# Sheet1_Overview.net
KiCad netlist of a schematic drawn in Altium Designer
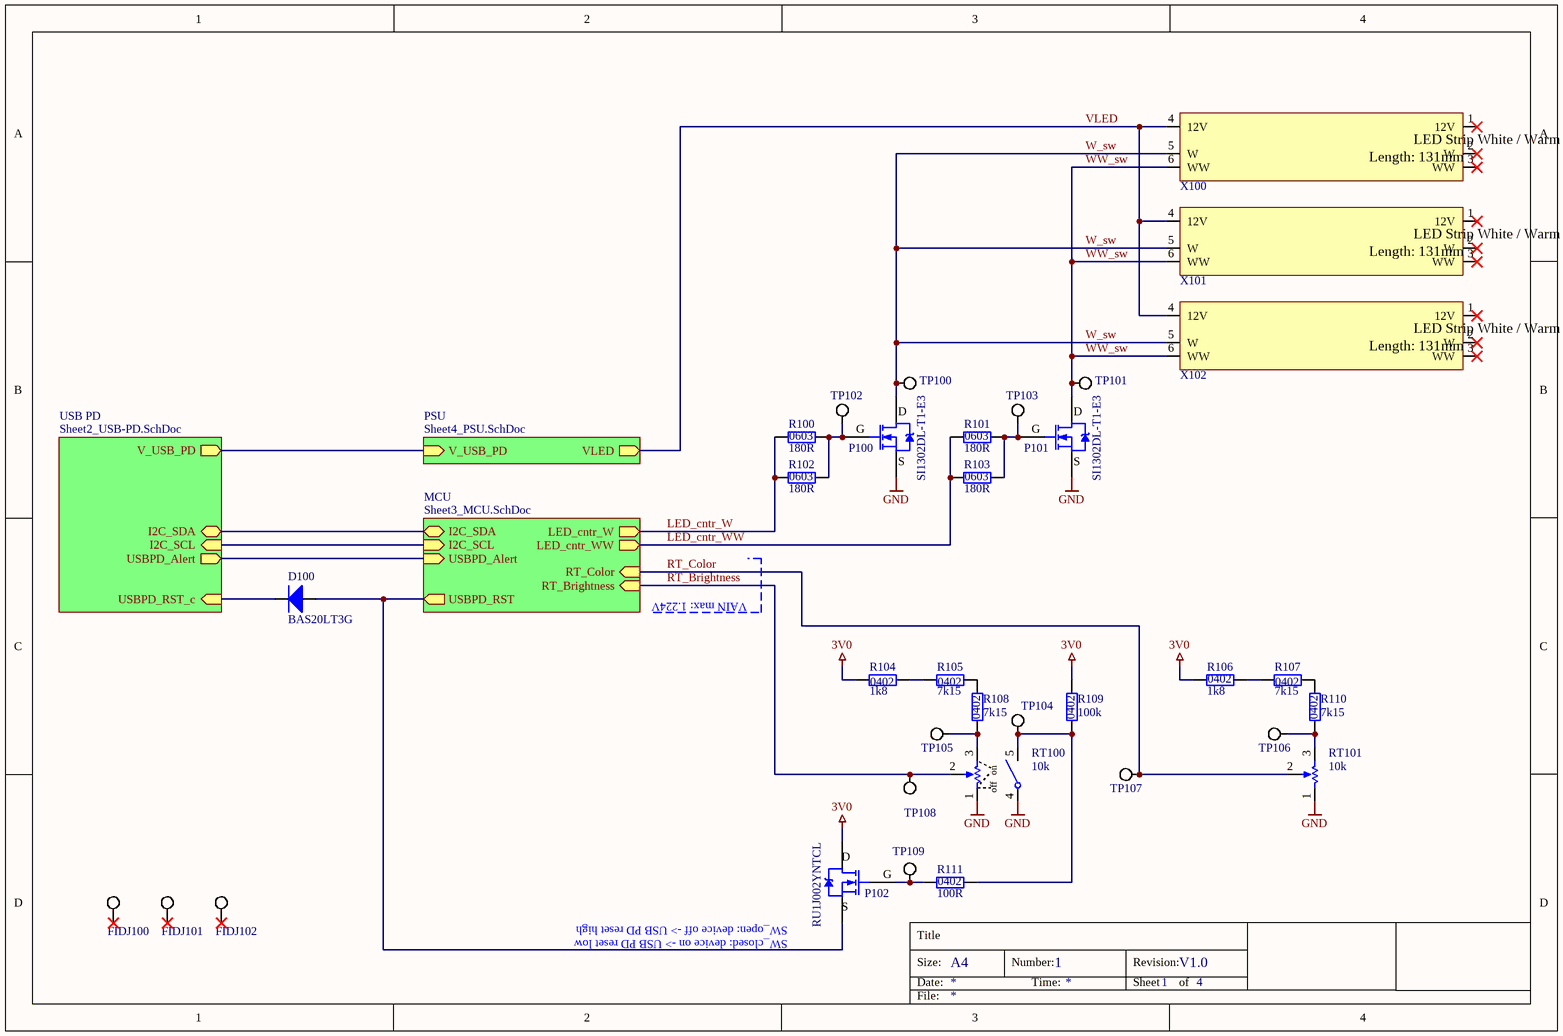
[diagram p0: Sheet1_Overview.SchDoc]

(export (version "E")
  (design (tool "Eeschema 10.0.6"))
  (components
    (comp (ref "D100")
      (value "BAS20LT3G")
      (footprint "SOT-23-3")
      (description "DIODE GP 200V 200MA SOT23-3")
      (fields (field (name "MANUFACTURER") "onsemi") (field (name "MANUFACTURER PART NUMBER") "BAS20LT3G"))
      (libsource (lib "CS_Part_Library") (part "D_LL_200V_200mA"))
    )
    (comp (ref "FIDJ100")
      (value "Fiducial")
      (footprint "FIDJ_1mm")
      (description "Fiducal 1mm")
      (libsource (lib "CS_Part_Library") (part "FIDJ_1mm"))
    )
    (comp (ref "FIDJ101")
      (value "Fiducial")
      (footprint "FIDJ_1mm")
      (description "Fiducal 1mm")
      (libsource (lib "CS_Part_Library") (part "FIDJ_1mm"))
    )
    (comp (ref "FIDJ102")
      (value "Fiducial")
      (footprint "FIDJ_1mm")
      (description "Fiducal 1mm")
      (libsource (lib "CS_Part_Library") (part "FIDJ_1mm"))
    )
    (comp (ref "P100")
      (value "P NMOS 30V 600mA")
      (footprint "SOT-323")
      (description "MOSFET N-CH 30V 600MA SC70-3")
      (fields
        (field (name "MANUFACTURER") "Vishay Siliconix")
        (field (name "MANUFACTURER PART NUMBER") "SI1302DL-T1-E3")
      )
      (libsource (lib "CS_Part_Library") (part "P_NCH_30V_280mW"))
    )
    (comp (ref "P101")
      (value "P NMOS 30V 600mA")
      (footprint "SOT-323")
      (description "MOSFET N-CH 30V 600MA SC70-3")
      (fields
        (field (name "MANUFACTURER") "Vishay Siliconix")
        (field (name "MANUFACTURER PART NUMBER") "SI1302DL-T1-E3")
      )
      (libsource (lib "CS_Part_Library") (part "P_NCH_30V_280mW"))
    )
    (comp (ref "P102")
      (value "P_NCH_50V_150mW")
      (footprint "UMT3F")
      (description "MOSFET N-CH 50V 200MA UMT3F")
      (fields
        (field (name "MANUFACTURER") "Rohm Semiconductor")
        (field (name "MANUFACTURER PART NUMBER") "RU1J002YNTCL")
      )
      (libsource (lib "CS_Part_Library") (part "P_NCH_50V_150mW"))
    )
    (comp (ref "R100")
      (value "R 180R 0603")
      (footprint "0603")
      (description "RES 180 OHM 1% 1/10W 0603")
      (fields
        (field (name "MANUFACTURER") "Stackpole Electronics Inc")
        (field (name "MANUFACTURER PART NUMBER") "RMCF0603FT180R")
        (field (name "RESISTANCE") "180R")
      )
      (libsource (lib "CS_Part_Library") (part "R_180R_0603"))
    )
    (comp (ref "R101")
      (value "R 180R 0603")
      (footprint "0603")
      (description "RES 180 OHM 1% 1/10W 0603")
      (fields
        (field (name "MANUFACTURER") "Stackpole Electronics Inc")
        (field (name "MANUFACTURER PART NUMBER") "RMCF0603FT180R")
        (field (name "RESISTANCE") "180R")
      )
      (libsource (lib "CS_Part_Library") (part "R_180R_0603"))
    )
    (comp (ref "R102")
      (value "R 180R 0603")
      (footprint "0603")
      (description "RES 180 OHM 1% 1/10W 0603")
      (fields
        (field (name "MANUFACTURER") "Stackpole Electronics Inc")
        (field (name "MANUFACTURER PART NUMBER") "RMCF0603FT180R")
        (field (name "RESISTANCE") "180R")
      )
      (libsource (lib "CS_Part_Library") (part "R_180R_0603"))
    )
    (comp (ref "R103")
      (value "R 180R 0603")
      (footprint "0603")
      (description "RES 180 OHM 1% 1/10W 0603")
      (fields
        (field (name "MANUFACTURER") "Stackpole Electronics Inc")
        (field (name "MANUFACTURER PART NUMBER") "RMCF0603FT180R")
        (field (name "RESISTANCE") "180R")
      )
      (libsource (lib "CS_Part_Library") (part "R_180R_0603"))
    )
    (comp (ref "R104")
      (value "R 1k8 0402")
      (footprint "0402")
      (description "RES 1.8K OHM 1% 1/16W 0402")
      (fields
        (field (name "MANUFACTURER") "Stackpole Electronics Inc")
        (field (name "MANUFACTURER PART NUMBER") "RMCF0402FT1K80")
        (field (name "RESISTANCE") "1k8")
      )
      (libsource (lib "") (part "R_1k8_0402_1"))
    )
    (comp (ref "R105")
      (value "R 7k15 0402")
      (footprint "0402")
      (description "RES 7.15K OHM 1% 1/16W 0402")
      (fields
        (field (name "MANUFACTURER") "Stackpole Electronics Inc")
        (field (name "MANUFACTURER PART NUMBER") "RMCF0402FT7K15")
        (field (name "RESISTANCE") "7k15")
      )
      (libsource (lib "") (part "R_7k15_0402_1"))
    )
    (comp (ref "R106")
      (value "R 1k8 0402")
      (footprint "0402")
      (description "RES 1.8K OHM 1% 1/16W 0402")
      (fields
        (field (name "MANUFACTURER") "Stackpole Electronics Inc")
        (field (name "MANUFACTURER PART NUMBER") "RMCF0402FT1K80")
        (field (name "RESISTANCE") "1k8")
      )
      (libsource (lib "CS_Part_Library") (part "R_1k8_0402"))
    )
    (comp (ref "R107")
      (value "R 7k15 0402")
      (footprint "0402")
      (description "RES 7.15K OHM 1% 1/16W 0402")
      (fields
        (field (name "MANUFACTURER") "Stackpole Electronics Inc")
        (field (name "MANUFACTURER PART NUMBER") "RMCF0402FT7K15")
        (field (name "RESISTANCE") "7k15")
      )
      (libsource (lib "") (part "R_7k15_0402_1"))
    )
    (comp (ref "R108")
      (value "R 7k15 0402")
      (footprint "0402")
      (description "RES 7.15K OHM 1% 1/16W 0402")
      (fields
        (field (name "MANUFACTURER") "Stackpole Electronics Inc")
        (field (name "MANUFACTURER PART NUMBER") "RMCF0402FT7K15")
        (field (name "RESISTANCE") "7k15")
      )
      (libsource (lib "CS_Part_Library") (part "R_7k15_0402"))
    )
    (comp (ref "R109")
      (value "R 100k 0402")
      (footprint "0402")
      (description "RES 100K OHM 5% 1/16W 0402")
      (fields
        (field (name "MANUFACTURER") "YAGEO")
        (field (name "MANUFACTURER PART NUMBER") "RC0402JR-07100KL")
        (field (name "RESISTANCE") "100k")
      )
      (libsource (lib "CS_Part_Library") (part "R_100k_0402"))
    )
    (comp (ref "R110")
      (value "R 7k15 0402")
      (footprint "0402")
      (description "RES 7.15K OHM 1% 1/16W 0402")
      (fields
        (field (name "MANUFACTURER") "Stackpole Electronics Inc")
        (field (name "MANUFACTURER PART NUMBER") "RMCF0402FT7K15")
        (field (name "RESISTANCE") "7k15")
      )
      (libsource (lib "CS_Part_Library") (part "R_7k15_0402"))
    )
    (comp (ref "R111")
      (value "R 100R 0402")
      (footprint "0402")
      (description "RES 100 OHM 1% 1/16W 0402")
      (fields
        (field (name "MANUFACTURER") "Stackpole Electronics Inc")
        (field (name "MANUFACTURER PART NUMBER") "RMCF0402FT100R")
        (field (name "RESISTANCE") "100R")
      )
      (libsource (lib "CS_Part_Library") (part "R_100R_0402"))
    )
    (comp (ref "RT100")
      (value "10k")
      (footprint "RT_P091S-F*20")
      (description "POT 10K OHM 1/20W PLASTIC LINEAR")
      (fields
        (field (name "MANUFACTURER") "TT Electronics/BI")
        (field (name "MANUFACTURER PART NUMBER") "P091S-FC20BR10K")
      )
      (libsource (lib "CS_Part_Library") (part "RT_10k_SW_V"))
    )
    (comp (ref "RT101")
      (value "10k")
      (footprint "RT_P091N-F*25")
      (description "POT 10K OHM 1/20W PLASTIC LINEAR")
      (fields
        (field (name "MANUFACTURER") "TT Electronics/BI")
        (field (name "MANUFACTURER PART NUMBER") "P091N-FC25BR10K")
      )
      (libsource (lib "CS_Part_Library") (part "RT_10k_V"))
    )
    (comp (ref "TP100")
      (value "TP")
      (footprint "TP_1mm")
      (description "Test Point 1mm")
      (libsource (lib "CS_Part_Library") (part "TP_1mm"))
    )
    (comp (ref "TP101")
      (value "TP")
      (footprint "TP_1mm")
      (description "Test Point 1mm")
      (libsource (lib "CS_Part_Library") (part "TP_1mm"))
    )
    (comp (ref "TP102")
      (value "TP")
      (footprint "TP_1mm")
      (description "Test Point 1mm")
      (libsource (lib "CS_Part_Library") (part "TP_1mm"))
    )
    (comp (ref "TP103")
      (value "TP")
      (footprint "TP_1mm")
      (description "Test Point 1mm")
      (libsource (lib "CS_Part_Library") (part "TP_1mm"))
    )
    (comp (ref "TP104")
      (value "TP")
      (footprint "TP_1mm")
      (description "Test Point 1mm")
      (libsource (lib "CS_Part_Library") (part "TP_1mm"))
    )
    (comp (ref "TP105")
      (value "TP")
      (footprint "TP_1mm")
      (description "Test Point 1mm")
      (libsource (lib "CS_Part_Library") (part "TP_1mm"))
    )
    (comp (ref "TP106")
      (value "TP")
      (footprint "TP_1mm")
      (description "Test Point 1mm")
      (libsource (lib "CS_Part_Library") (part "TP_1mm"))
    )
    (comp (ref "TP107")
      (value "TP")
      (footprint "TP_1mm")
      (description "Test Point 1mm")
      (libsource (lib "CS_Part_Library") (part "TP_1mm"))
    )
    (comp (ref "TP108")
      (value "TP")
      (footprint "TP_1mm")
      (description "Test Point 1mm")
      (libsource (lib "CS_Part_Library") (part "TP_1mm"))
    )
    (comp (ref "TP109")
      (value "TP")
      (footprint "TP_1mm")
      (description "Test Point 1mm")
      (libsource (lib "CS_Part_Library") (part "TP_1mm"))
    )
    (comp (ref "X100")
      (value "LED Strip")
      (footprint "LED_Strip_COB44-076")
      (description "revoART, 12V COB LED Streifen - einstellbare Farbtemperatur - alle 1,3cm teilbar - 10mm breit")
      (fields (field (name "MANUFACTURER") "revoART") (field (name "MANUFACTURER PART NUMBER") "COB44-076"))
      (libsource (lib "CS_Part_Library") (part "LED_Strip_2WH_131mm"))
    )
    (comp (ref "X101")
      (value "LED Strip")
      (footprint "LED_Strip_COB44-076")
      (description "revoART, 12V COB LED Streifen - einstellbare Farbtemperatur - alle 1,3cm teilbar - 10mm breit")
      (fields (field (name "MANUFACTURER") "revoART") (field (name "MANUFACTURER PART NUMBER") "COB44-076"))
      (libsource (lib "CS_Part_Library") (part "LED_Strip_2WH_131mm"))
    )
    (comp (ref "X102")
      (value "LED Strip")
      (footprint "LED_Strip_COB44-076")
      (description "revoART, 12V COB LED Streifen - einstellbare Farbtemperatur - alle 1,3cm teilbar - 10mm breit")
      (fields (field (name "MANUFACTURER") "revoART") (field (name "MANUFACTURER PART NUMBER") "COB44-076"))
      (libsource (lib "CS_Part_Library") (part "LED_Strip_2WH_131mm"))
    )
  )
  (nets
    (net (code "3") (name "/LED_cntr_W") (class "Default")
      (node (ref "R100") (pin "1") (pinfunction "1_1") (pintype "passive"))
      (node (ref "R102") (pin "1") (pinfunction "1_1") (pintype "passive"))
    )
    (net (code "4") (name "/LED_cntr_WW") (class "Default")
      (node (ref "R101") (pin "1") (pinfunction "1_1") (pintype "passive"))
      (node (ref "R103") (pin "1") (pinfunction "1_1") (pintype "passive"))
    )
    (net (code "5") (name "/RT_Brightness") (class "Default")
      (node (ref "RT100") (pin "2") (pinfunction "2_2") (pintype "passive"))
      (node (ref "TP108") (pin "1") (pinfunction "TP_1") (pintype "passive"))
    )
    (net (code "6") (name "/RT_Color") (class "Default")
      (node (ref "RT101") (pin "2") (pinfunction "2_2") (pintype "passive"))
      (node (ref "TP107") (pin "1") (pinfunction "TP_1") (pintype "passive"))
    )
    (net (code "8") (name "/USBPD_RST") (class "Default")
      (node (ref "D100") (pin "1") (pinfunction "A_1") (pintype "passive"))
      (node (ref "P102") (pin "2") (pinfunction "S_2") (pintype "passive"))
    )
    (net (code "9") (name "/USBPD_RST_c") (class "Default")
      (node (ref "D100") (pin "3") (pinfunction "K_3") (pintype "passive"))
    )
    (net (code "10") (name "/VLED") (class "Default")
      (node (ref "X100") (pin "4") (pinfunction "12V_4") (pintype "passive"))
      (node (ref "X101") (pin "4") (pinfunction "12V_4") (pintype "passive"))
      (node (ref "X102") (pin "4") (pinfunction "12V_4") (pintype "passive"))
    )
    (net (code "12") (name "/WW_sw") (class "Default")
      (node (ref "P101") (pin "3") (pinfunction "D_3") (pintype "passive"))
      (node (ref "TP101") (pin "1") (pinfunction "TP_1") (pintype "passive"))
      (node (ref "X100") (pin "6") (pinfunction "WW_6") (pintype "passive"))
      (node (ref "X101") (pin "6") (pinfunction "WW_6") (pintype "passive"))
      (node (ref "X102") (pin "6") (pinfunction "WW_6") (pintype "passive"))
    )
    (net (code "13") (name "/W_sw") (class "Default")
      (node (ref "P100") (pin "3") (pinfunction "D_3") (pintype "passive"))
      (node (ref "TP100") (pin "1") (pinfunction "TP_1") (pintype "passive"))
      (node (ref "X100") (pin "5") (pinfunction "W_5") (pintype "passive"))
      (node (ref "X101") (pin "5") (pinfunction "W_5") (pintype "passive"))
      (node (ref "X102") (pin "5") (pinfunction "W_5") (pintype "passive"))
    )
    (net (code "14") (name "3V0") (class "Default")
      (node (ref "P102") (pin "3") (pinfunction "D_3") (pintype "passive"))
      (node (ref "R104") (pin "2") (pinfunction "2_2") (pintype "passive"))
      (node (ref "R106") (pin "1") (pinfunction "1_1") (pintype "passive"))
      (node (ref "R109") (pin "2") (pinfunction "2_2") (pintype "passive"))
    )
    (net (code "15") (name "GND") (class "Default")
      (node (ref "P100") (pin "2") (pinfunction "S_2") (pintype "passive"))
      (node (ref "P101") (pin "2") (pinfunction "S_2") (pintype "passive"))
      (node (ref "RT100") (pin "1") (pinfunction "1_1") (pintype "passive"))
      (node (ref "RT100") (pin "4") (pinfunction "4_4") (pintype "passive"))
      (node (ref "RT101") (pin "1") (pinfunction "1_1") (pintype "passive"))
    )
    (net (code "16") (name "Net-(P100-G)") (class "Default")
      (node (ref "P100") (pin "1") (pinfunction "G_1") (pintype "passive"))
      (node (ref "R100") (pin "2") (pinfunction "2_2") (pintype "passive"))
      (node (ref "R102") (pin "2") (pinfunction "2_2") (pintype "passive"))
      (node (ref "TP102") (pin "1") (pinfunction "TP_1") (pintype "passive"))
    )
    (net (code "17") (name "Net-(P101-G)") (class "Default")
      (node (ref "P101") (pin "1") (pinfunction "G_1") (pintype "passive"))
      (node (ref "R101") (pin "2") (pinfunction "2_2") (pintype "passive"))
      (node (ref "R103") (pin "2") (pinfunction "2_2") (pintype "passive"))
      (node (ref "TP103") (pin "1") (pinfunction "TP_1") (pintype "passive"))
    )
    (net (code "18") (name "Net-(P102-G)") (class "Default")
      (node (ref "P102") (pin "1") (pinfunction "G_1") (pintype "passive"))
      (node (ref "R111") (pin "1") (pinfunction "1_1") (pintype "passive"))
      (node (ref "TP109") (pin "1") (pinfunction "TP_1") (pintype "passive"))
    )
    (net (code "19") (name "Net-(R104-Pad1)") (class "Default")
      (node (ref "R104") (pin "1") (pinfunction "1_1") (pintype "passive"))
      (node (ref "R105") (pin "2") (pinfunction "2_2") (pintype "passive"))
    )
    (net (code "20") (name "Net-(R105-Pad1)") (class "Default")
      (node (ref "R105") (pin "1") (pinfunction "1_1") (pintype "passive"))
      (node (ref "R108") (pin "2") (pinfunction "2_2") (pintype "passive"))
    )
    (net (code "21") (name "Net-(R106-Pad2)") (class "Default")
      (node (ref "R106") (pin "2") (pinfunction "2_2") (pintype "passive"))
      (node (ref "R107") (pin "2") (pinfunction "2_2") (pintype "passive"))
    )
    (net (code "22") (name "Net-(R107-Pad1)") (class "Default")
      (node (ref "R107") (pin "1") (pinfunction "1_1") (pintype "passive"))
      (node (ref "R110") (pin "2") (pinfunction "2_2") (pintype "passive"))
    )
    (net (code "23") (name "Net-(TP104-TP)") (class "Default")
      (node (ref "R109") (pin "1") (pinfunction "1_1") (pintype "passive"))
      (node (ref "R111") (pin "2") (pinfunction "2_2") (pintype "passive"))
      (node (ref "RT100") (pin "5") (pinfunction "5_5") (pintype "passive"))
      (node (ref "TP104") (pin "1") (pinfunction "TP_1") (pintype "passive"))
    )
    (net (code "24") (name "Net-(TP105-TP)") (class "Default")
      (node (ref "R108") (pin "1") (pinfunction "1_1") (pintype "passive"))
      (node (ref "RT100") (pin "3") (pinfunction "3_3") (pintype "passive"))
      (node (ref "TP105") (pin "1") (pinfunction "TP_1") (pintype "passive"))
    )
    (net (code "25") (name "Net-(TP106-TP)") (class "Default")
      (node (ref "R110") (pin "1") (pinfunction "1_1") (pintype "passive"))
      (node (ref "RT101") (pin "3") (pinfunction "3_3") (pintype "passive"))
      (node (ref "TP106") (pin "1") (pinfunction "TP_1") (pintype "passive"))
    )
    (net (code "26") (name "unconnected-(FIDJ100-Pad1)") (class "Default")
      (node (ref "FIDJ100") (pin "1") (pinfunction "1_1") (pintype "passive+no_connect"))
    )
    (net (code "27") (name "unconnected-(FIDJ101-Pad1)") (class "Default")
      (node (ref "FIDJ101") (pin "1") (pinfunction "1_1") (pintype "passive+no_connect"))
    )
    (net (code "28") (name "unconnected-(FIDJ102-Pad1)") (class "Default")
      (node (ref "FIDJ102") (pin "1") (pinfunction "1_1") (pintype "passive+no_connect"))
    )
    (net (code "29") (name "unconnected-(X100-12V-Pad1)") (class "Default")
      (node (ref "X100") (pin "1") (pinfunction "12V_1") (pintype "passive+no_connect"))
    )
    (net (code "30") (name "unconnected-(X100-W-Pad2)") (class "Default")
      (node (ref "X100") (pin "2") (pinfunction "W_2") (pintype "passive+no_connect"))
    )
    (net (code "31") (name "unconnected-(X100-WW-Pad3)") (class "Default")
      (node (ref "X100") (pin "3") (pinfunction "WW_3") (pintype "passive+no_connect"))
    )
    (net (code "32") (name "unconnected-(X101-12V-Pad1)") (class "Default")
      (node (ref "X101") (pin "1") (pinfunction "12V_1") (pintype "passive+no_connect"))
    )
    (net (code "33") (name "unconnected-(X101-W-Pad2)") (class "Default")
      (node (ref "X101") (pin "2") (pinfunction "W_2") (pintype "passive+no_connect"))
    )
    (net (code "34") (name "unconnected-(X101-WW-Pad3)") (class "Default")
      (node (ref "X101") (pin "3") (pinfunction "WW_3") (pintype "passive+no_connect"))
    )
    (net (code "35") (name "unconnected-(X102-12V-Pad1)") (class "Default")
      (node (ref "X102") (pin "1") (pinfunction "12V_1") (pintype "passive+no_connect"))
    )
    (net (code "36") (name "unconnected-(X102-W-Pad2)") (class "Default")
      (node (ref "X102") (pin "2") (pinfunction "W_2") (pintype "passive+no_connect"))
    )
    (net (code "37") (name "unconnected-(X102-WW-Pad3)") (class "Default")
      (node (ref "X102") (pin "3") (pinfunction "WW_3") (pintype "passive+no_connect"))
    )
  )
)
